# In-Out.net
KiCad netlist of a schematic drawn in Altium Designer
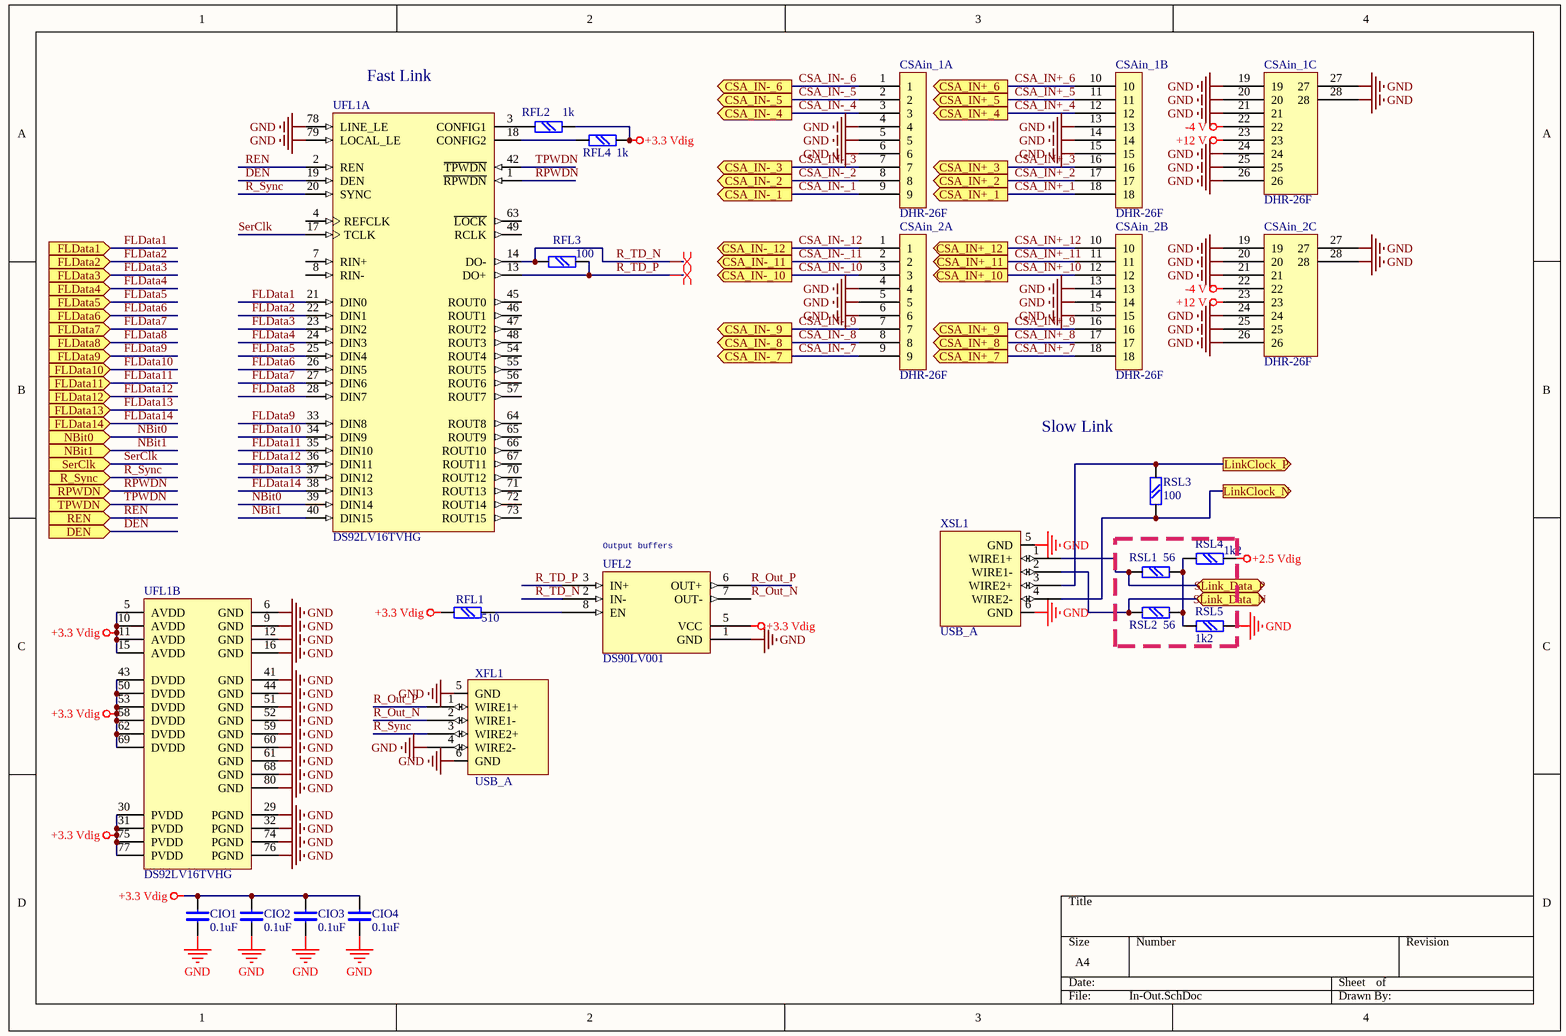
[diagram p0: In-Out.SchDoc]

(export (version "E")
  (design (tool "Eeschema 10.0.6"))
  (components
    (comp (ref "CIO1") (value "0.1uF") (footprint "chip0603") (libsource (lib "*") (part "C")))
    (comp (ref "CIO2") (value "0.1uF") (footprint "chip0603") (libsource (lib "*") (part "C")))
    (comp (ref "CIO3") (value "0.1uF") (footprint "chip0603") (libsource (lib "*") (part "C")))
    (comp (ref "CIO4") (value "0.1uF") (footprint "chip0603") (libsource (lib "*") (part "C")))
    (comp (ref "CSAin_1")
      (value "DHR-26F")
      (footprint "DHR-F-26")
      (libsource (lib "vDevice") (part "DHR-26F"))
    )
    (comp (ref "CSAin_2")
      (value "DHR-26F")
      (footprint "DHR-F-26")
      (libsource (lib "vDevice") (part "DHR-26F"))
    )
    (comp (ref "RFL1") (value "510") (footprint "chip0603") (libsource (lib "") (part "R_1")))
    (comp (ref "RFL2") (value "1k") (footprint "chip0603") (libsource (lib "vDevice") (part "R")))
    (comp (ref "RFL3") (value "100") (footprint "chip0603") (libsource (lib "") (part "R_1")))
    (comp (ref "RFL4") (value "1k") (footprint "chip0603") (libsource (lib "vDevice") (part "R")))
    (comp (ref "RSL1") (value "56") (footprint "chip0603") (libsource (lib "*") (part "R")))
    (comp (ref "RSL2") (value "56") (footprint "chip0603") (libsource (lib "*") (part "R")))
    (comp (ref "RSL3") (value "100") (footprint "chip0603") (libsource (lib "*") (part "R")))
    (comp (ref "RSL4") (value "1k2") (footprint "chip0603") (libsource (lib "*") (part "R")))
    (comp (ref "RSL5") (value "1k2") (footprint "chip0603") (libsource (lib "*") (part "R")))
    (comp (ref "UFL1")
      (value "DS92LV16TVHG")
      (footprint "VHG80A_N")
      (description "16-Bit Bus LVDS Serializer/Deserializer - 25 - 80 MHz, 80-pin LQFP")
      (fields
        (field (name "MANUFACTURER") "National Semiconductor")
        (field (name "PUBLISHER") "Altium Limited")
      )
      (libsource (lib "NSC Interface") (part "DS92LV16TVHG"))
    )
    (comp (ref "UFL2")
      (value "DS90LV001")
      (footprint "8SO200")
      (libsource (lib "vDigital") (part "DS90LV001"))
    )
    (comp (ref "XFL1") (value "USB_A") (footprint "USB2.5-2H4B") (libsource (lib "*") (part "USB_A")))
    (comp (ref "XSL1") (value "USB_A") (footprint "USB2.5-2H4B") (libsource (lib "Con USB") (part "USB_A")))
  )
  (nets
    (net (code "1") (name "+2.5 Vdig") (class "Default")
      (node (ref "RSL4") (pin "2") (pinfunction "2_2") (pintype "passive"))
    )
    (net (code "2") (name "+3.3 Vdig") (class "Default")
      (node (ref "CIO1") (pin "2") (pinfunction "2_2") (pintype "passive"))
      (node (ref "CIO2") (pin "2") (pinfunction "2_2") (pintype "passive"))
      (node (ref "CIO3") (pin "2") (pinfunction "2_2") (pintype "passive"))
      (node (ref "CIO4") (pin "2") (pinfunction "2_2") (pintype "passive"))
      (node (ref "RFL1") (pin "1") (pinfunction "1_1") (pintype "passive"))
      (node (ref "RFL2") (pin "2") (pinfunction "2_2") (pintype "passive"))
      (node (ref "RFL4") (pin "2") (pinfunction "2_2") (pintype "passive"))
      (node (ref "UFL1") (pin "10") (pinfunction "AVDD_10") (pintype "power_in"))
      (node (ref "UFL1") (pin "11") (pinfunction "AVDD_11") (pintype "power_in"))
      (node (ref "UFL1") (pin "15") (pinfunction "AVDD_15") (pintype "power_in"))
      (node (ref "UFL1") (pin "30") (pinfunction "PVDD_30") (pintype "power_in"))
      (node (ref "UFL1") (pin "31") (pinfunction "PVDD_31") (pintype "power_in"))
      (node (ref "UFL1") (pin "43") (pinfunction "DVDD_43") (pintype "power_in"))
      (node (ref "UFL1") (pin "5") (pinfunction "AVDD_5") (pintype "power_in"))
      (node (ref "UFL1") (pin "50") (pinfunction "DVDD_50") (pintype "power_in"))
      (node (ref "UFL1") (pin "53") (pinfunction "DVDD_53") (pintype "power_in"))
      (node (ref "UFL1") (pin "58") (pinfunction "DVDD_58") (pintype "power_in"))
      (node (ref "UFL1") (pin "62") (pinfunction "DVDD_62") (pintype "power_in"))
      (node (ref "UFL1") (pin "69") (pinfunction "DVDD_69") (pintype "power_in"))
      (node (ref "UFL1") (pin "75") (pinfunction "PVDD_75") (pintype "power_in"))
      (node (ref "UFL1") (pin "77") (pinfunction "PVDD_77") (pintype "power_in"))
      (node (ref "UFL2") (pin "5") (pinfunction "VCC_5") (pintype "power_in"))
    )
    (net (code "3") (name "+12 V") (class "Default")
      (node (ref "CSAin_1") (pin "23") (pinfunction "23_23") (pintype "passive"))
      (node (ref "CSAin_2") (pin "23") (pinfunction "23_23") (pintype "passive"))
    )
    (net (code "4") (name "-4 V") (class "Default")
      (node (ref "CSAin_1") (pin "22") (pinfunction "22_22") (pintype "passive"))
      (node (ref "CSAin_2") (pin "22") (pinfunction "22_22") (pintype "passive"))
    )
    (net (code "5") (name "/CSA_IN+_1") (class "Default")
      (node (ref "CSAin_1") (pin "18") (pinfunction "18_18") (pintype "passive"))
    )
    (net (code "6") (name "/CSA_IN+_2") (class "Default")
      (node (ref "CSAin_1") (pin "17") (pinfunction "17_17") (pintype "passive"))
    )
    (net (code "7") (name "/CSA_IN+_3") (class "Default")
      (node (ref "CSAin_1") (pin "16") (pinfunction "16_16") (pintype "passive"))
    )
    (net (code "8") (name "/CSA_IN+_4") (class "Default")
      (node (ref "CSAin_1") (pin "12") (pinfunction "12_12") (pintype "passive"))
    )
    (net (code "9") (name "/CSA_IN+_5") (class "Default")
      (node (ref "CSAin_1") (pin "11") (pinfunction "11_11") (pintype "passive"))
    )
    (net (code "10") (name "/CSA_IN+_6") (class "Default")
      (node (ref "CSAin_1") (pin "10") (pinfunction "10_10") (pintype "passive"))
    )
    (net (code "11") (name "/CSA_IN+_7") (class "Default")
      (node (ref "CSAin_2") (pin "18") (pinfunction "18_18") (pintype "passive"))
    )
    (net (code "12") (name "/CSA_IN+_8") (class "Default")
      (node (ref "CSAin_2") (pin "17") (pinfunction "17_17") (pintype "passive"))
    )
    (net (code "13") (name "/CSA_IN+_9") (class "Default")
      (node (ref "CSAin_2") (pin "16") (pinfunction "16_16") (pintype "passive"))
    )
    (net (code "14") (name "/CSA_IN+_10") (class "Default")
      (node (ref "CSAin_2") (pin "12") (pinfunction "12_12") (pintype "passive"))
    )
    (net (code "15") (name "/CSA_IN+_11") (class "Default")
      (node (ref "CSAin_2") (pin "11") (pinfunction "11_11") (pintype "passive"))
    )
    (net (code "16") (name "/CSA_IN+_12") (class "Default")
      (node (ref "CSAin_2") (pin "10") (pinfunction "10_10") (pintype "passive"))
    )
    (net (code "17") (name "/CSA_IN-_1") (class "Default")
      (node (ref "CSAin_1") (pin "9") (pinfunction "9_9") (pintype "passive"))
    )
    (net (code "18") (name "/CSA_IN-_2") (class "Default")
      (node (ref "CSAin_1") (pin "8") (pinfunction "8_8") (pintype "passive"))
    )
    (net (code "19") (name "/CSA_IN-_3") (class "Default")
      (node (ref "CSAin_1") (pin "7") (pinfunction "7_7") (pintype "passive"))
    )
    (net (code "20") (name "/CSA_IN-_4") (class "Default")
      (node (ref "CSAin_1") (pin "3") (pinfunction "3_3") (pintype "passive"))
    )
    (net (code "21") (name "/CSA_IN-_5") (class "Default")
      (node (ref "CSAin_1") (pin "2") (pinfunction "2_2") (pintype "passive"))
    )
    (net (code "22") (name "/CSA_IN-_6") (class "Default")
      (node (ref "CSAin_1") (pin "1") (pinfunction "1_1") (pintype "passive"))
    )
    (net (code "23") (name "/CSA_IN-_7") (class "Default")
      (node (ref "CSAin_2") (pin "9") (pinfunction "9_9") (pintype "passive"))
    )
    (net (code "24") (name "/CSA_IN-_8") (class "Default")
      (node (ref "CSAin_2") (pin "8") (pinfunction "8_8") (pintype "passive"))
    )
    (net (code "25") (name "/CSA_IN-_9") (class "Default")
      (node (ref "CSAin_2") (pin "7") (pinfunction "7_7") (pintype "passive"))
    )
    (net (code "26") (name "/CSA_IN-_10") (class "Default")
      (node (ref "CSAin_2") (pin "3") (pinfunction "3_3") (pintype "passive"))
    )
    (net (code "27") (name "/CSA_IN-_11") (class "Default")
      (node (ref "CSAin_2") (pin "2") (pinfunction "2_2") (pintype "passive"))
    )
    (net (code "28") (name "/CSA_IN-_12") (class "Default")
      (node (ref "CSAin_2") (pin "1") (pinfunction "1_1") (pintype "passive"))
    )
    (net (code "29") (name "/DEN") (class "Default")
      (node (ref "UFL1") (pin "19") (pinfunction "DEN_19") (pintype "input"))
    )
    (net (code "30") (name "/FLData1") (class "Default")
      (node (ref "UFL1") (pin "21") (pinfunction "DIN0_21") (pintype "input"))
    )
    (net (code "31") (name "/FLData2") (class "Default")
      (node (ref "UFL1") (pin "22") (pinfunction "DIN1_22") (pintype "input"))
    )
    (net (code "32") (name "/FLData3") (class "Default")
      (node (ref "UFL1") (pin "23") (pinfunction "DIN2_23") (pintype "input"))
    )
    (net (code "33") (name "/FLData4") (class "Default")
      (node (ref "UFL1") (pin "24") (pinfunction "DIN3_24") (pintype "input"))
    )
    (net (code "34") (name "/FLData5") (class "Default")
      (node (ref "UFL1") (pin "25") (pinfunction "DIN4_25") (pintype "input"))
    )
    (net (code "35") (name "/FLData6") (class "Default")
      (node (ref "UFL1") (pin "26") (pinfunction "DIN5_26") (pintype "input"))
    )
    (net (code "36") (name "/FLData7") (class "Default")
      (node (ref "UFL1") (pin "27") (pinfunction "DIN6_27") (pintype "input"))
    )
    (net (code "37") (name "/FLData8") (class "Default")
      (node (ref "UFL1") (pin "28") (pinfunction "DIN7_28") (pintype "input"))
    )
    (net (code "38") (name "/FLData9") (class "Default")
      (node (ref "UFL1") (pin "33") (pinfunction "DIN8_33") (pintype "input"))
    )
    (net (code "39") (name "/FLData10") (class "Default")
      (node (ref "UFL1") (pin "34") (pinfunction "DIN9_34") (pintype "input"))
    )
    (net (code "40") (name "/FLData11") (class "Default")
      (node (ref "UFL1") (pin "35") (pinfunction "DIN10_35") (pintype "input"))
    )
    (net (code "41") (name "/FLData12") (class "Default")
      (node (ref "UFL1") (pin "36") (pinfunction "DIN11_36") (pintype "input"))
    )
    (net (code "42") (name "/FLData13") (class "Default")
      (node (ref "UFL1") (pin "37") (pinfunction "DIN12_37") (pintype "input"))
    )
    (net (code "43") (name "/FLData14") (class "Default")
      (node (ref "UFL1") (pin "38") (pinfunction "DIN13_38") (pintype "input"))
    )
    (net (code "44") (name "/LinkClock_N") (class "Default")
      (node (ref "RSL3") (pin "1") (pinfunction "1_1") (pintype "passive"))
      (node (ref "XSL1") (pin "4") (pinfunction "WIRE2-_4") (pintype "bidirectional"))
    )
    (net (code "45") (name "/LinkClock_P") (class "Default")
      (node (ref "RSL3") (pin "2") (pinfunction "2_2") (pintype "passive"))
      (node (ref "XSL1") (pin "3") (pinfunction "WIRE2+_3") (pintype "bidirectional"))
    )
    (net (code "46") (name "/NBit0") (class "Default")
      (node (ref "UFL1") (pin "39") (pinfunction "DIN14_39") (pintype "input"))
    )
    (net (code "47") (name "/NBit1") (class "Default")
      (node (ref "UFL1") (pin "40") (pinfunction "DIN15_40") (pintype "input"))
    )
    (net (code "48") (name "/REN") (class "Default")
      (node (ref "UFL1") (pin "2") (pinfunction "REN_2") (pintype "input"))
    )
    (net (code "49") (name "/RPWDN") (class "Default")
      (node (ref "UFL1") (pin "1") (pinfunction "~{RPWDN}_1") (pintype "input"))
    )
    (net (code "50") (name "/R_Out_N") (class "Default")
      (node (ref "UFL2") (pin "7") (pinfunction "OUT-_7") (pintype "output"))
      (node (ref "XFL1") (pin "2") (pinfunction "WIRE1-_2") (pintype "bidirectional"))
    )
    (net (code "51") (name "/R_Out_P") (class "Default")
      (node (ref "UFL2") (pin "6") (pinfunction "OUT+_6") (pintype "output"))
      (node (ref "XFL1") (pin "1") (pinfunction "WIRE1+_1") (pintype "bidirectional"))
    )
    (net (code "52") (name "/R_Sync") (class "Default")
      (node (ref "UFL1") (pin "20") (pinfunction "SYNC_20") (pintype "input"))
      (node (ref "XFL1") (pin "3") (pinfunction "WIRE2+_3") (pintype "bidirectional"))
    )
    (net (code "53") (name "/R_TD_N") (class "Default")
      (node (ref "RFL3") (pin "1") (pinfunction "1_1") (pintype "passive"))
      (node (ref "UFL1") (pin "14") (pinfunction "DO-_14") (pintype "output"))
      (node (ref "UFL2") (pin "2") (pinfunction "IN-_2") (pintype "input"))
    )
    (net (code "54") (name "/R_TD_P") (class "Default")
      (node (ref "RFL3") (pin "2") (pinfunction "2_2") (pintype "passive"))
      (node (ref "UFL1") (pin "13") (pinfunction "DO+_13") (pintype "output"))
      (node (ref "UFL2") (pin "3") (pinfunction "IN+_3") (pintype "input"))
    )
    (net (code "55") (name "/SLink_Data_N") (class "Default")
      (node (ref "RSL2") (pin "2") (pinfunction "2_2") (pintype "passive"))
      (node (ref "XSL1") (pin "2") (pinfunction "WIRE1-_2") (pintype "bidirectional"))
    )
    (net (code "56") (name "/SLink_Data_P") (class "Default")
      (node (ref "RSL1") (pin "2") (pinfunction "2_2") (pintype "passive"))
      (node (ref "XSL1") (pin "1") (pinfunction "WIRE1+_1") (pintype "bidirectional"))
    )
    (net (code "57") (name "/SerClk") (class "Default")
      (node (ref "UFL1") (pin "17") (pinfunction "TCLK_17") (pintype "input"))
    )
    (net (code "58") (name "/TPWDN") (class "Default")
      (node (ref "UFL1") (pin "42") (pinfunction "~{TPWDN}_42") (pintype "input"))
    )
    (net (code "59") (name "GND") (class "Default")
      (node (ref "CIO1") (pin "1") (pinfunction "1_1") (pintype "passive"))
      (node (ref "CIO2") (pin "1") (pinfunction "1_1") (pintype "passive"))
      (node (ref "CIO3") (pin "1") (pinfunction "1_1") (pintype "passive"))
      (node (ref "CIO4") (pin "1") (pinfunction "1_1") (pintype "passive"))
      (node (ref "CSAin_1") (pin "13") (pinfunction "13_13") (pintype "passive"))
      (node (ref "CSAin_1") (pin "14") (pinfunction "14_14") (pintype "passive"))
      (node (ref "CSAin_1") (pin "15") (pinfunction "15_15") (pintype "passive"))
      (node (ref "CSAin_1") (pin "19") (pinfunction "19_19") (pintype "passive"))
      (node (ref "CSAin_1") (pin "20") (pinfunction "20_20") (pintype "passive"))
      (node (ref "CSAin_1") (pin "21") (pinfunction "21_21") (pintype "passive"))
      (node (ref "CSAin_1") (pin "24") (pinfunction "24_24") (pintype "passive"))
      (node (ref "CSAin_1") (pin "25") (pinfunction "25_25") (pintype "passive"))
      (node (ref "CSAin_1") (pin "26") (pinfunction "26_26") (pintype "passive"))
      (node (ref "CSAin_1") (pin "27") (pinfunction "27_27") (pintype "passive"))
      (node (ref "CSAin_1") (pin "28") (pinfunction "28_28") (pintype "passive"))
      (node (ref "CSAin_1") (pin "4") (pinfunction "4_4") (pintype "passive"))
      (node (ref "CSAin_1") (pin "5") (pinfunction "5_5") (pintype "passive"))
      (node (ref "CSAin_1") (pin "6") (pinfunction "6_6") (pintype "passive"))
      (node (ref "CSAin_2") (pin "13") (pinfunction "13_13") (pintype "passive"))
      (node (ref "CSAin_2") (pin "14") (pinfunction "14_14") (pintype "passive"))
      (node (ref "CSAin_2") (pin "15") (pinfunction "15_15") (pintype "passive"))
      (node (ref "CSAin_2") (pin "19") (pinfunction "19_19") (pintype "passive"))
      (node (ref "CSAin_2") (pin "20") (pinfunction "20_20") (pintype "passive"))
      (node (ref "CSAin_2") (pin "21") (pinfunction "21_21") (pintype "passive"))
      (node (ref "CSAin_2") (pin "24") (pinfunction "24_24") (pintype "passive"))
      (node (ref "CSAin_2") (pin "25") (pinfunction "25_25") (pintype "passive"))
      (node (ref "CSAin_2") (pin "26") (pinfunction "26_26") (pintype "passive"))
      (node (ref "CSAin_2") (pin "27") (pinfunction "27_27") (pintype "passive"))
      (node (ref "CSAin_2") (pin "28") (pinfunction "28_28") (pintype "passive"))
      (node (ref "CSAin_2") (pin "4") (pinfunction "4_4") (pintype "passive"))
      (node (ref "CSAin_2") (pin "5") (pinfunction "5_5") (pintype "passive"))
      (node (ref "CSAin_2") (pin "6") (pinfunction "6_6") (pintype "passive"))
      (node (ref "RSL5") (pin "1") (pinfunction "1_1") (pintype "passive"))
      (node (ref "UFL1") (pin "12") (pinfunction "AGND_12") (pintype "power_in"))
      (node (ref "UFL1") (pin "16") (pinfunction "AGND_16") (pintype "power_in"))
      (node (ref "UFL1") (pin "29") (pinfunction "PGND_29") (pintype "power_in"))
      (node (ref "UFL1") (pin "32") (pinfunction "PGND_32") (pintype "power_in"))
      (node (ref "UFL1") (pin "41") (pinfunction "DGND_41") (pintype "power_in"))
      (node (ref "UFL1") (pin "44") (pinfunction "DGND_44") (pintype "power_in"))
      (node (ref "UFL1") (pin "51") (pinfunction "DGND_51") (pintype "power_in"))
      (node (ref "UFL1") (pin "52") (pinfunction "DGND_52") (pintype "power_in"))
      (node (ref "UFL1") (pin "59") (pinfunction "DGND_59") (pintype "power_in"))
      (node (ref "UFL1") (pin "6") (pinfunction "AGND_6") (pintype "power_in"))
      (node (ref "UFL1") (pin "60") (pinfunction "DGND_60") (pintype "power_in"))
      (node (ref "UFL1") (pin "61") (pinfunction "DGND_61") (pintype "power_in"))
      (node (ref "UFL1") (pin "68") (pinfunction "DGND_68") (pintype "power_in"))
      (node (ref "UFL1") (pin "74") (pinfunction "PGND_74") (pintype "power_in"))
      (node (ref "UFL1") (pin "76") (pinfunction "PGND_76") (pintype "power_in"))
      (node (ref "UFL1") (pin "78") (pinfunction "LINE_LE_78") (pintype "input"))
      (node (ref "UFL1") (pin "79") (pinfunction "LOCAL_LE_79") (pintype "input"))
      (node (ref "UFL1") (pin "80") (pinfunction "DGND_80") (pintype "power_in"))
      (node (ref "UFL1") (pin "9") (pinfunction "AGND_9") (pintype "power_in"))
      (node (ref "UFL2") (pin "1") (pinfunction "GND_1") (pintype "power_in"))
      (node (ref "XFL1") (pin "4") (pinfunction "WIRE2-_4") (pintype "bidirectional"))
      (node (ref "XFL1") (pin "5") (pinfunction "GND_5") (pintype "passive"))
      (node (ref "XFL1") (pin "6") (pinfunction "GND_6") (pintype "passive"))
      (node (ref "XSL1") (pin "5") (pinfunction "GND_5") (pintype "passive"))
      (node (ref "XSL1") (pin "6") (pinfunction "GND_6") (pintype "passive"))
    )
    (net (code "60") (name "Net-(RSL1-Pad1)") (class "Default")
      (node (ref "RSL1") (pin "1") (pinfunction "1_1") (pintype "passive"))
      (node (ref "RSL2") (pin "1") (pinfunction "1_1") (pintype "passive"))
      (node (ref "RSL4") (pin "1") (pinfunction "1_1") (pintype "passive"))
      (node (ref "RSL5") (pin "2") (pinfunction "2_2") (pintype "passive"))
    )
    (net (code "61") (name "Net-(UFL1A-CONFIG1)") (class "Default")
      (node (ref "RFL2") (pin "1") (pinfunction "1_1") (pintype "passive"))
      (node (ref "UFL1") (pin "3") (pinfunction "CONFIG1_3") (pintype "passive"))
    )
    (net (code "62") (name "Net-(UFL1A-CONFIG2)") (class "Default")
      (node (ref "RFL4") (pin "1") (pinfunction "1_1") (pintype "passive"))
      (node (ref "UFL1") (pin "18") (pinfunction "CONFIG2_18") (pintype "passive"))
    )
    (net (code "63") (name "Net-(UFL2-EN)") (class "Default")
      (node (ref "RFL1") (pin "2") (pinfunction "2_2") (pintype "passive"))
      (node (ref "UFL2") (pin "8") (pinfunction "EN_8") (pintype "input"))
    )
    (net (code "64") (name "unconnected-(UFL1A-RCLK-Pad49)") (class "Default")
      (node (ref "UFL1") (pin "49") (pinfunction "RCLK_49") (pintype "output"))
    )
    (net (code "65") (name "unconnected-(UFL1A-REFCLK-Pad4)") (class "Default")
      (node (ref "UFL1") (pin "4") (pinfunction "REFCLK_4") (pintype "input"))
    )
    (net (code "66") (name "unconnected-(UFL1A-RIN+-Pad7)") (class "Default")
      (node (ref "UFL1") (pin "7") (pinfunction "RIN+_7") (pintype "input"))
    )
    (net (code "67") (name "unconnected-(UFL1A-RIN--Pad8)") (class "Default")
      (node (ref "UFL1") (pin "8") (pinfunction "RIN-_8") (pintype "input"))
    )
    (net (code "68") (name "unconnected-(UFL1A-ROUT0-Pad45)") (class "Default")
      (node (ref "UFL1") (pin "45") (pinfunction "ROUT0_45") (pintype "output"))
    )
    (net (code "69") (name "unconnected-(UFL1A-ROUT1-Pad46)") (class "Default")
      (node (ref "UFL1") (pin "46") (pinfunction "ROUT1_46") (pintype "output"))
    )
    (net (code "70") (name "unconnected-(UFL1A-ROUT2-Pad47)") (class "Default")
      (node (ref "UFL1") (pin "47") (pinfunction "ROUT2_47") (pintype "output"))
    )
    (net (code "71") (name "unconnected-(UFL1A-ROUT3-Pad48)") (class "Default")
      (node (ref "UFL1") (pin "48") (pinfunction "ROUT3_48") (pintype "output"))
    )
    (net (code "72") (name "unconnected-(UFL1A-ROUT4-Pad54)") (class "Default")
      (node (ref "UFL1") (pin "54") (pinfunction "ROUT4_54") (pintype "output"))
    )
    (net (code "73") (name "unconnected-(UFL1A-ROUT5-Pad55)") (class "Default")
      (node (ref "UFL1") (pin "55") (pinfunction "ROUT5_55") (pintype "output"))
    )
    (net (code "74") (name "unconnected-(UFL1A-ROUT6-Pad56)") (class "Default")
      (node (ref "UFL1") (pin "56") (pinfunction "ROUT6_56") (pintype "output"))
    )
    (net (code "75") (name "unconnected-(UFL1A-ROUT7-Pad57)") (class "Default")
      (node (ref "UFL1") (pin "57") (pinfunction "ROUT7_57") (pintype "output"))
    )
    (net (code "76") (name "unconnected-(UFL1A-ROUT8-Pad64)") (class "Default")
      (node (ref "UFL1") (pin "64") (pinfunction "ROUT8_64") (pintype "output"))
    )
    (net (code "77") (name "unconnected-(UFL1A-ROUT9-Pad65)") (class "Default")
      (node (ref "UFL1") (pin "65") (pinfunction "ROUT9_65") (pintype "output"))
    )
    (net (code "78") (name "unconnected-(UFL1A-ROUT10-Pad66)") (class "Default")
      (node (ref "UFL1") (pin "66") (pinfunction "ROUT10_66") (pintype "output"))
    )
    (net (code "79") (name "unconnected-(UFL1A-ROUT11-Pad67)") (class "Default")
      (node (ref "UFL1") (pin "67") (pinfunction "ROUT11_67") (pintype "output"))
    )
    (net (code "80") (name "unconnected-(UFL1A-ROUT12-Pad70)") (class "Default")
      (node (ref "UFL1") (pin "70") (pinfunction "ROUT12_70") (pintype "output"))
    )
    (net (code "81") (name "unconnected-(UFL1A-ROUT13-Pad71)") (class "Default")
      (node (ref "UFL1") (pin "71") (pinfunction "ROUT13_71") (pintype "output"))
    )
    (net (code "82") (name "unconnected-(UFL1A-ROUT14-Pad72)") (class "Default")
      (node (ref "UFL1") (pin "72") (pinfunction "ROUT14_72") (pintype "output"))
    )
    (net (code "83") (name "unconnected-(UFL1A-ROUT15-Pad73)") (class "Default")
      (node (ref "UFL1") (pin "73") (pinfunction "ROUT15_73") (pintype "output"))
    )
    (net (code "84") (name "unconnected-(UFL1A-~{LOCK}-Pad63)") (class "Default")
      (node (ref "UFL1") (pin "63") (pinfunction "~{LOCK}_63") (pintype "output"))
    )
  )
)
